# car_sheet.net
KiCad netlist of a schematic drawn in Altium Designer
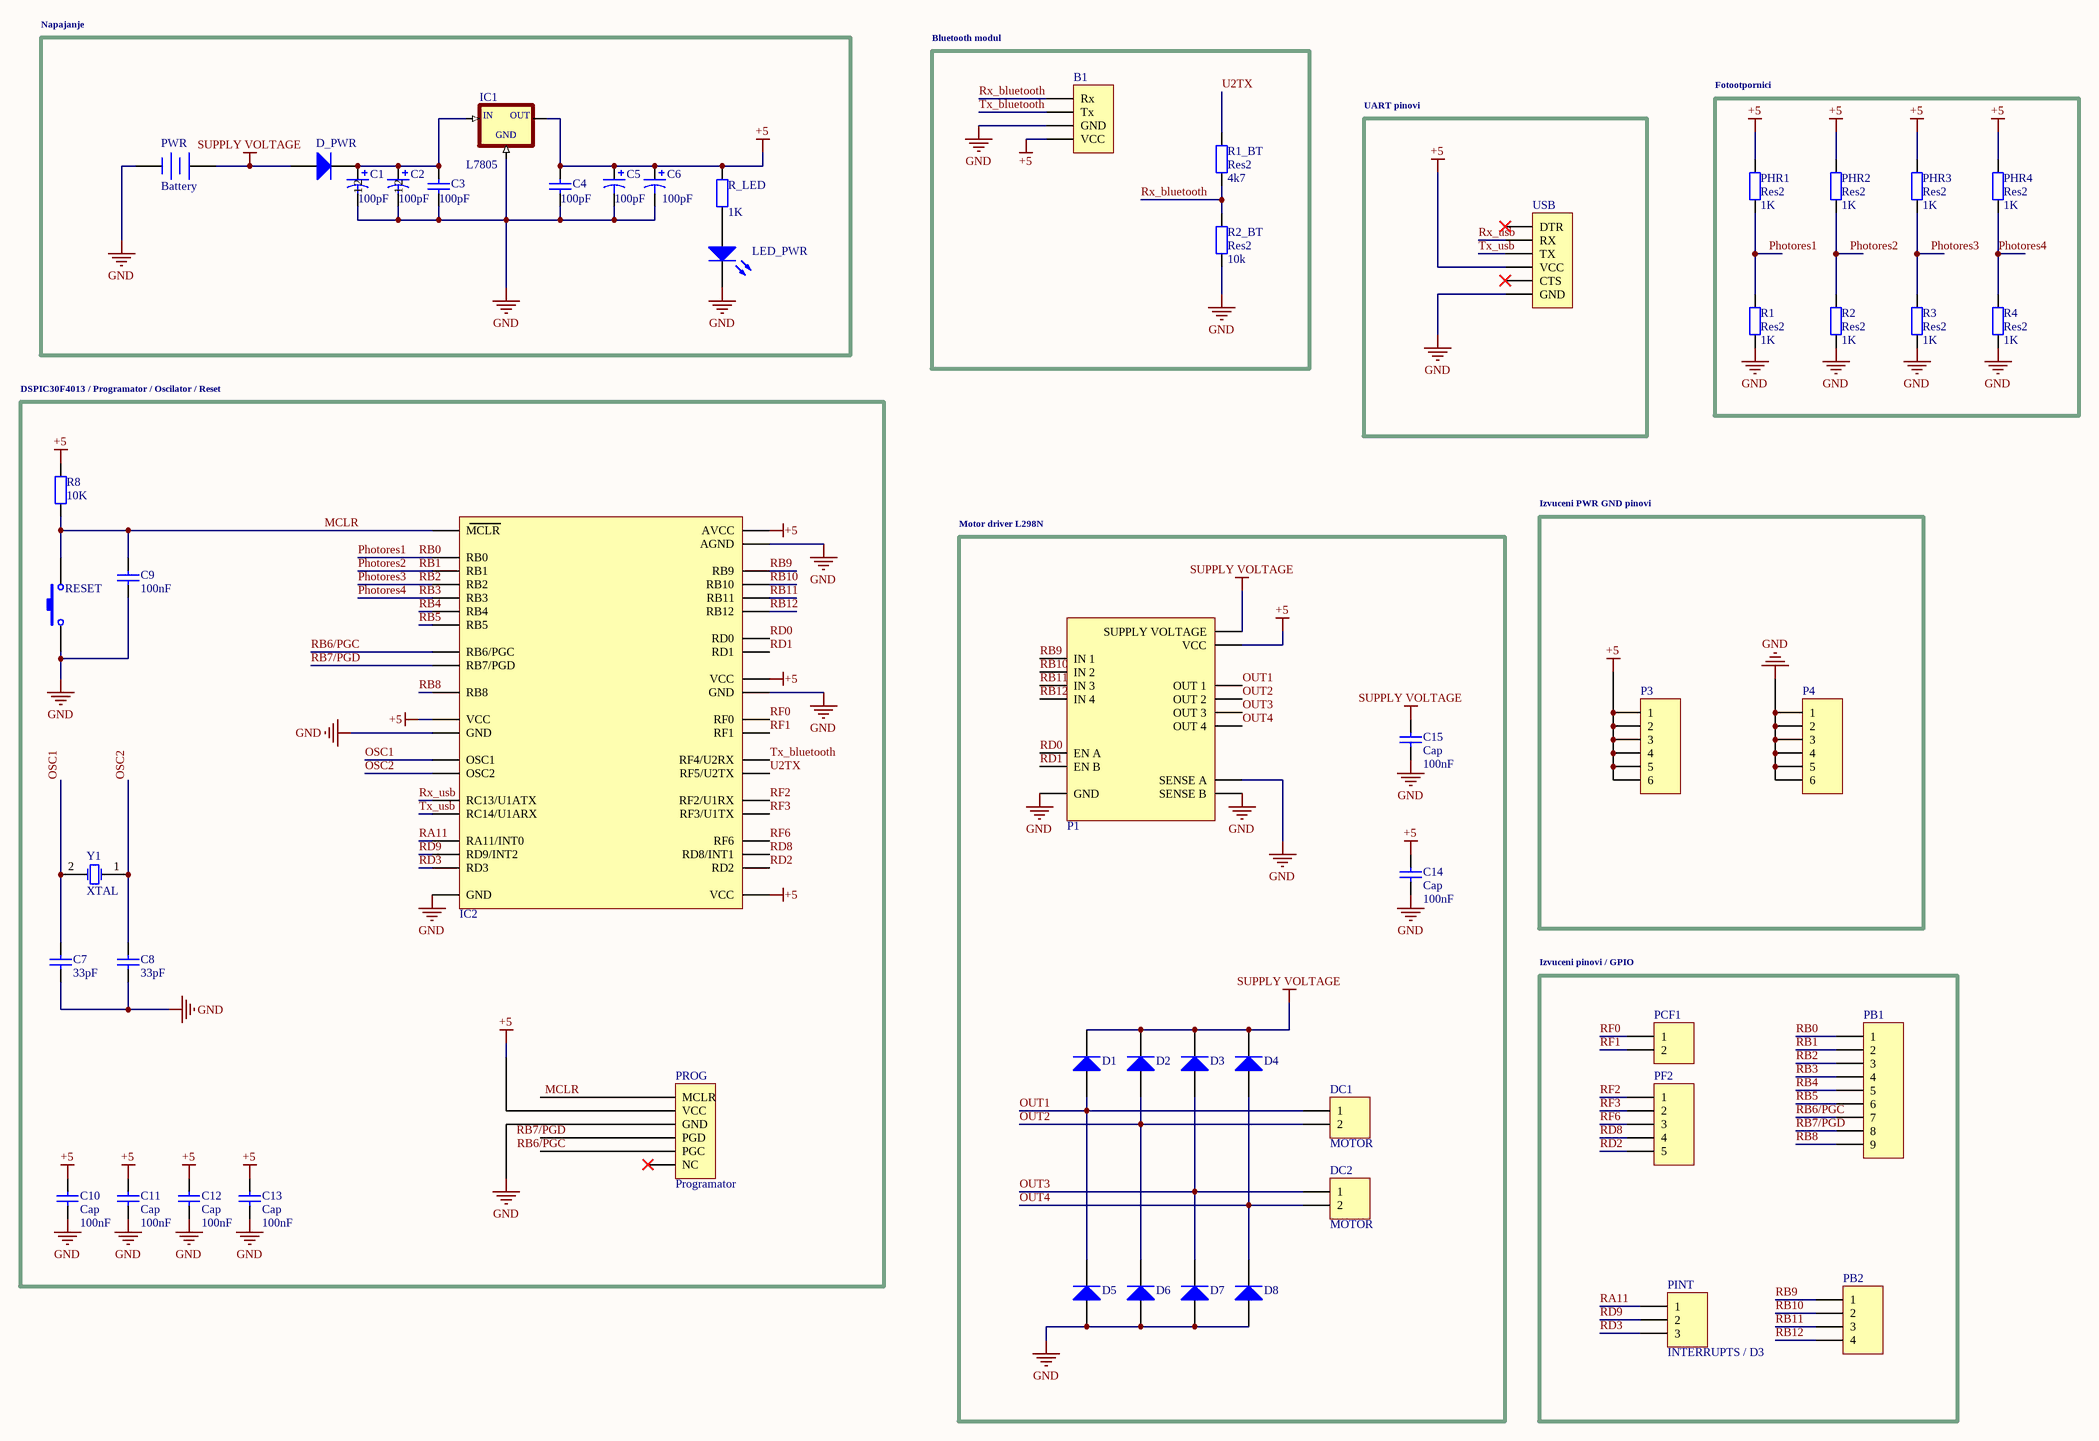
[diagram p0: car_sheet.SchDoc]

(export (version "E")
  (design (tool "Eeschema 10.0.6"))
  (components
    (comp (ref "B1")
      (value "~")
      (footprint "HDR1X4")
      (description "Header, 4-Pin")
      (fields (field (name "PUBLISHER") "Altium Limited"))
      (libsource (lib "Miscellaneous Connectors") (part "Header 4"))
    )
    (comp (ref "C1")
      (value "100pF")
      (footprint "POL_CAP")
      (description "Polarized Capacitor (Radial)")
      (fields (field (name "PUBLISHER") "Altium Limited"))
      (libsource (lib "Miscellaneous Devices") (part "Cap Pol1"))
    )
    (comp (ref "C2")
      (value "100pF")
      (footprint "POL_CAP")
      (description "Polarized Capacitor (Radial)")
      (fields (field (name "PUBLISHER") "Altium Limited"))
      (libsource (lib "Miscellaneous Devices") (part "Cap Pol1"))
    )
    (comp (ref "C3")
      (value "100pF")
      (footprint "RAD-0.3")
      (description "Capacitor")
      (fields (field (name "PUBLISHER") "Altium Limited"))
      (libsource (lib "Miscellaneous Devices") (part "Cap"))
    )
    (comp (ref "C4")
      (value "100pF")
      (footprint "RAD-0.3")
      (description "Capacitor")
      (fields (field (name "PUBLISHER") "Altium Limited"))
      (libsource (lib "Miscellaneous Devices") (part "Cap"))
    )
    (comp (ref "C5")
      (value "100pF")
      (footprint "POL_CAP")
      (description "Polarized Capacitor (Radial)")
      (fields (field (name "PUBLISHER") "Altium Limited"))
      (libsource (lib "") (part "Cap Pol1_1"))
    )
    (comp (ref "C6")
      (value "100pF")
      (footprint "POL_CAP")
      (description "Polarized Capacitor (Radial)")
      (fields (field (name "PUBLISHER") "Altium Limited"))
      (libsource (lib "") (part "Cap Pol1_1"))
    )
    (comp (ref "C7")
      (value "33pF")
      (footprint "RAD-0.3")
      (description "Capacitor")
      (fields (field (name "Comment") "Cap") (field (name "PUBLISHER") "Altium Limited"))
      (libsource (lib "Miscellaneous Devices") (part "Cap"))
    )
    (comp (ref "C8")
      (value "33pF")
      (footprint "RAD-0.3")
      (description "Capacitor")
      (fields (field (name "Comment") "Cap") (field (name "PUBLISHER") "Altium Limited"))
      (libsource (lib "Miscellaneous Devices") (part "Cap"))
    )
    (comp (ref "C9")
      (value "100nF")
      (footprint "RAD-0.3")
      (description "Capacitor")
      (fields (field (name "Comment") "Cap") (field (name "PUBLISHER") "Altium Limited"))
      (libsource (lib "Miscellaneous Devices") (part "Cap"))
    )
    (comp (ref "C10")
      (value "Cap")
      (footprint "RAD-0.3")
      (description "Capacitor")
      (fields (field (name "ALTIUM_VALUE") "100nF") (field (name "PUBLISHER") "Altium Limited"))
      (libsource (lib "Miscellaneous Devices") (part "Cap"))
    )
    (comp (ref "C11")
      (value "Cap")
      (footprint "RAD-0.3")
      (description "Capacitor")
      (fields (field (name "ALTIUM_VALUE") "100nF") (field (name "PUBLISHER") "Altium Limited"))
      (libsource (lib "Miscellaneous Devices") (part "Cap"))
    )
    (comp (ref "C12")
      (value "Cap")
      (footprint "RAD-0.3")
      (description "Capacitor")
      (fields (field (name "ALTIUM_VALUE") "100nF") (field (name "PUBLISHER") "Altium Limited"))
      (libsource (lib "Miscellaneous Devices") (part "Cap"))
    )
    (comp (ref "C13")
      (value "Cap")
      (footprint "RAD-0.3")
      (description "Capacitor")
      (fields (field (name "ALTIUM_VALUE") "100nF") (field (name "PUBLISHER") "Altium Limited"))
      (libsource (lib "Miscellaneous Devices") (part "Cap"))
    )
    (comp (ref "C14")
      (value "Cap")
      (footprint "RAD-0.3")
      (description "Capacitor")
      (fields (field (name "ALTIUM_VALUE") "100nF") (field (name "PUBLISHER") "Altium Limited"))
      (libsource (lib "Miscellaneous Devices") (part "Cap"))
    )
    (comp (ref "C15")
      (value "Cap")
      (footprint "RAD-0.3")
      (description "Capacitor")
      (fields (field (name "ALTIUM_VALUE") "100nF") (field (name "PUBLISHER") "Altium Limited"))
      (libsource (lib "Miscellaneous Devices") (part "Cap"))
    )
    (comp (ref "D1")
      (value "Diode 1N914")
      (footprint "DO-35")
      (description "High Conductance Fast Diode")
      (fields (field (name "PUBLISHER") "Altium Limited"))
      (libsource (lib "Miscellaneous Devices") (part "Diode 1N914"))
    )
    (comp (ref "D2")
      (value "Diode 1N914")
      (footprint "DO-35")
      (description "High Conductance Fast Diode")
      (fields (field (name "PUBLISHER") "Altium Limited"))
      (libsource (lib "Miscellaneous Devices") (part "Diode 1N914"))
    )
    (comp (ref "D3")
      (value "Diode 1N914")
      (footprint "DO-35")
      (description "High Conductance Fast Diode")
      (fields (field (name "PUBLISHER") "Altium Limited"))
      (libsource (lib "Miscellaneous Devices") (part "Diode 1N914"))
    )
    (comp (ref "D4")
      (value "Diode 1N914")
      (footprint "DO-35")
      (description "High Conductance Fast Diode")
      (fields (field (name "PUBLISHER") "Altium Limited"))
      (libsource (lib "Miscellaneous Devices") (part "Diode 1N914"))
    )
    (comp (ref "D5")
      (value "Diode 1N914")
      (footprint "DO-35")
      (description "High Conductance Fast Diode")
      (fields (field (name "PUBLISHER") "Altium Limited"))
      (libsource (lib "Miscellaneous Devices") (part "Diode 1N914"))
    )
    (comp (ref "D6")
      (value "Diode 1N914")
      (footprint "DO-35")
      (description "High Conductance Fast Diode")
      (fields (field (name "PUBLISHER") "Altium Limited"))
      (libsource (lib "Miscellaneous Devices") (part "Diode 1N914"))
    )
    (comp (ref "D7")
      (value "Diode 1N914")
      (footprint "DO-35")
      (description "High Conductance Fast Diode")
      (fields (field (name "PUBLISHER") "Altium Limited"))
      (libsource (lib "Miscellaneous Devices") (part "Diode 1N914"))
    )
    (comp (ref "D8")
      (value "Diode 1N914")
      (footprint "DO-35")
      (description "High Conductance Fast Diode")
      (fields (field (name "PUBLISHER") "Altium Limited"))
      (libsource (lib "Miscellaneous Devices") (part "Diode 1N914"))
    )
    (comp (ref "DC1")
      (value "MOTOR")
      (footprint "HDR1X2")
      (description "Header, 2-Pin")
      (fields (field (name "PUBLISHER") "Altium Limited"))
      (libsource (lib "Miscellaneous Connectors") (part "Header 2"))
    )
    (comp (ref "DC2")
      (value "MOTOR")
      (footprint "HDR1X2")
      (description "Header, 2-Pin")
      (fields (field (name "PUBLISHER") "Altium Limited"))
      (libsource (lib "Miscellaneous Connectors") (part "Header 2"))
    )
    (comp (ref "D_PWR")
      (value "~")
      (footprint "DO-41")
      (description "1 Amp General Purpose Rectifier")
      (fields (field (name "PUBLISHER") "Altium Limited"))
      (libsource (lib "Miscellaneous Devices") (part "Diode 1N4007"))
    )
    (comp (ref "IC1")
      (value "L7805")
      (footprint "TO-220FP_STM")
      (description "Linear Voltage Regulator IC 1 Output 1.5A D2PAK")
      (fields (field (name "MF") "STMicroelectronics"))
      (libsource (lib "L7805") (part "L7805"))
    )
    (comp (ref "IC2")
      (value "dsPIC30F4013")
      (footprint "PDIP40_600MC_MCH")
      (libsource (lib "LibLTC") (part "IC_40"))
    )
    (comp (ref "LED_PWR")
      (value "~")
      (footprint "HDR1X2")
      (description "Typical RED GaAs LED")
      (fields (field (name "PUBLISHER") "Altium Limited"))
      (libsource (lib "Miscellaneous Devices") (part "LED1"))
    )
    (comp (ref "P1") (value "L298N") (footprint "Multiwatt15_V_STM") (libsource (lib "LibRC") (part "L298N")))
    (comp (ref "P3")
      (value "~")
      (footprint "HDR1X6")
      (description "Header, 6-Pin")
      (fields (field (name "PUBLISHER") "Altium Limited"))
      (libsource (lib "Miscellaneous Connectors") (part "Header 6"))
    )
    (comp (ref "P4")
      (value "~")
      (footprint "HDR1X6")
      (description "Header, 6-Pin")
      (fields (field (name "PUBLISHER") "Altium Limited"))
      (libsource (lib "Miscellaneous Connectors") (part "Header 6"))
    )
    (comp (ref "PB1")
      (value "~")
      (footprint "HDR1X9")
      (description "Header, 9-Pin")
      (fields (field (name "PUBLISHER") "Altium Limited"))
      (libsource (lib "Miscellaneous Connectors") (part "Header 9"))
    )
    (comp (ref "PB2")
      (value "~")
      (footprint "HDR1X4")
      (description "Header, 4-Pin")
      (fields (field (name "PUBLISHER") "Altium Limited"))
      (libsource (lib "Miscellaneous Connectors") (part "Header 4"))
    )
    (comp (ref "PCF1")
      (value "~")
      (footprint "HDR1X2")
      (description "Header, 2-Pin")
      (fields (field (name "PUBLISHER") "Altium Limited"))
      (libsource (lib "Miscellaneous Connectors") (part "Header 2"))
    )
    (comp (ref "PF2")
      (value "~")
      (footprint "HDR1X5")
      (description "Header, 5-Pin")
      (fields (field (name "PUBLISHER") "Altium Limited"))
      (libsource (lib "Miscellaneous Connectors") (part "Header 5"))
    )
    (comp (ref "PHR1")
      (value "Res2")
      (footprint "AXIAL-0.4")
      (description "Resistor")
      (fields (field (name "ALTIUM_VALUE") "1K") (field (name "PUBLISHER") "Altium Limited"))
      (libsource (lib "Miscellaneous Devices") (part "Res2"))
    )
    (comp (ref "PHR2")
      (value "Res2")
      (footprint "AXIAL-0.4")
      (description "Resistor")
      (fields (field (name "ALTIUM_VALUE") "1K") (field (name "PUBLISHER") "Altium Limited"))
      (libsource (lib "Miscellaneous Devices") (part "Res2"))
    )
    (comp (ref "PHR3")
      (value "Res2")
      (footprint "AXIAL-0.4")
      (description "Resistor")
      (fields (field (name "ALTIUM_VALUE") "1K") (field (name "PUBLISHER") "Altium Limited"))
      (libsource (lib "Miscellaneous Devices") (part "Res2"))
    )
    (comp (ref "PHR4")
      (value "Res2")
      (footprint "AXIAL-0.4")
      (description "Resistor")
      (fields (field (name "ALTIUM_VALUE") "1K") (field (name "PUBLISHER") "Altium Limited"))
      (libsource (lib "Miscellaneous Devices") (part "Res2"))
    )
    (comp (ref "PINT")
      (value "INTERRUPTS / D3")
      (footprint "HDR1X3")
      (description "Header, 3-Pin")
      (fields (field (name "PUBLISHER") "Altium Limited"))
      (libsource (lib "Miscellaneous Connectors") (part "Header 3"))
    )
    (comp (ref "PROG")
      (value "Programator")
      (footprint "HDR1X6")
      (description "Header, 6-Pin")
      (fields (field (name "PUBLISHER") "Altium Limited"))
      (libsource (lib "Miscellaneous Connectors") (part "Header 6"))
    )
    (comp (ref "PWR")
      (value "Battery")
      (footprint "BAT-2")
      (description "Multicell Battery")
      (fields (field (name "PUBLISHER") "Altium Limited"))
      (libsource (lib "Miscellaneous Devices") (part "Battery"))
    )
    (comp (ref "R1")
      (value "Res2")
      (footprint "AXIAL-0.4")
      (description "Resistor")
      (fields (field (name "ALTIUM_VALUE") "1K") (field (name "PUBLISHER") "Altium Limited"))
      (libsource (lib "Miscellaneous Devices") (part "Res2"))
    )
    (comp (ref "R1_BT")
      (value "Res2")
      (footprint "AXIAL-0.4")
      (description "Resistor")
      (fields (field (name "ALTIUM_VALUE") "4k7") (field (name "PUBLISHER") "Altium Limited"))
      (libsource (lib "Miscellaneous Devices") (part "Res2"))
    )
    (comp (ref "R2")
      (value "Res2")
      (footprint "AXIAL-0.4")
      (description "Resistor")
      (fields (field (name "ALTIUM_VALUE") "1K") (field (name "PUBLISHER") "Altium Limited"))
      (libsource (lib "Miscellaneous Devices") (part "Res2"))
    )
    (comp (ref "R2_BT")
      (value "Res2")
      (footprint "AXIAL-0.4")
      (description "Resistor")
      (fields (field (name "ALTIUM_VALUE") "10k") (field (name "PUBLISHER") "Altium Limited"))
      (libsource (lib "Miscellaneous Devices") (part "Res2"))
    )
    (comp (ref "R3")
      (value "Res2")
      (footprint "AXIAL-0.4")
      (description "Resistor")
      (fields (field (name "ALTIUM_VALUE") "1K") (field (name "PUBLISHER") "Altium Limited"))
      (libsource (lib "Miscellaneous Devices") (part "Res2"))
    )
    (comp (ref "R4")
      (value "Res2")
      (footprint "AXIAL-0.4")
      (description "Resistor")
      (fields (field (name "ALTIUM_VALUE") "1K") (field (name "PUBLISHER") "Altium Limited"))
      (libsource (lib "Miscellaneous Devices") (part "Res2"))
    )
    (comp (ref "R8")
      (value "10K")
      (footprint "AXIAL-0.4")
      (description "Resistor")
      (fields (field (name "Comment") "Res2") (field (name "PUBLISHER") "Altium Limited"))
      (libsource (lib "Miscellaneous Devices") (part "Res2"))
    )
    (comp (ref "RESET")
      (value "SW-PB")
      (footprint "SPST-2")
      (description "Switch")
      (fields (field (name "PUBLISHER") "Altium Limited"))
      (libsource (lib "Miscellaneous Devices") (part "SW-PB"))
    )
    (comp (ref "R_LED")
      (value "1K")
      (footprint "AXIAL-0.4")
      (description "Resistor")
      (fields (field (name "PUBLISHER") "Altium Limited"))
      (libsource (lib "Miscellaneous Devices") (part "Res2"))
    )
    (comp (ref "USB")
      (value "~")
      (footprint "HDR1X6")
      (description "Header, 6-Pin")
      (fields (field (name "PUBLISHER") "Altium Limited"))
      (libsource (lib "Miscellaneous Connectors") (part "Header 6"))
    )
    (comp (ref "Y1")
      (value "XTAL")
      (footprint "R38")
      (description "Crystal Oscillator")
      (fields (field (name "PUBLISHER") "Altium Limited"))
      (libsource (lib "Miscellaneous Devices") (part "XTAL"))
    )
  )
  (nets
    (net (code "1") (name "+5") (class "Default")
      (node (ref "B1") (pin "4") (pinfunction "4_4") (pintype "passive"))
      (node (ref "C10") (pin "1") (pinfunction "1_1") (pintype "passive"))
      (node (ref "C11") (pin "2") (pinfunction "2_2") (pintype "passive"))
      (node (ref "C12") (pin "2") (pinfunction "2_2") (pintype "passive"))
      (node (ref "C13") (pin "2") (pinfunction "2_2") (pintype "passive"))
      (node (ref "C14") (pin "2") (pinfunction "2_2") (pintype "passive"))
      (node (ref "C4") (pin "2") (pinfunction "2_2") (pintype "passive"))
      (node (ref "C5") (pin "1") (pinfunction "1_1") (pintype "passive"))
      (node (ref "C6") (pin "1") (pinfunction "1_1") (pintype "passive"))
      (node (ref "IC1") (pin "3") (pinfunction "OUT_3") (pintype "passive"))
      (node (ref "IC2") (pin "11") (pinfunction "VCC_11") (pintype "passive"))
      (node (ref "IC2") (pin "21") (pinfunction "VCC_21") (pintype "passive"))
      (node (ref "IC2") (pin "32") (pinfunction "VCC_32") (pintype "passive"))
      (node (ref "IC2") (pin "40") (pinfunction "AVCC_40") (pintype "passive"))
      (node (ref "P1") (pin "9") (pinfunction "VCC_9") (pintype "passive"))
      (node (ref "P3") (pin "1") (pinfunction "1_1") (pintype "passive"))
      (node (ref "P3") (pin "2") (pinfunction "2_2") (pintype "passive"))
      (node (ref "P3") (pin "3") (pinfunction "3_3") (pintype "passive"))
      (node (ref "P3") (pin "4") (pinfunction "4_4") (pintype "passive"))
      (node (ref "P3") (pin "5") (pinfunction "5_5") (pintype "passive"))
      (node (ref "P3") (pin "6") (pinfunction "6_6") (pintype "passive"))
      (node (ref "PHR1") (pin "2") (pinfunction "2_2") (pintype "passive"))
      (node (ref "PHR2") (pin "2") (pinfunction "2_2") (pintype "passive"))
      (node (ref "PHR3") (pin "2") (pinfunction "2_2") (pintype "passive"))
      (node (ref "PHR4") (pin "2") (pinfunction "2_2") (pintype "passive"))
      (node (ref "PROG") (pin "2") (pinfunction "2_2") (pintype "passive"))
      (node (ref "R8") (pin "2") (pinfunction "2_2") (pintype "passive"))
      (node (ref "R_LED") (pin "2") (pinfunction "2_2") (pintype "passive"))
      (node (ref "USB") (pin "4") (pinfunction "4_4") (pintype "passive"))
    )
    (net (code "2") (name "/MCLR") (class "Default")
      (node (ref "C9") (pin "1") (pinfunction "1_1") (pintype "passive"))
      (node (ref "IC2") (pin "1") (pinfunction "MCLR_1") (pintype "passive"))
      (node (ref "PROG") (pin "1") (pinfunction "1_1") (pintype "passive"))
      (node (ref "R8") (pin "1") (pinfunction "1_1") (pintype "passive"))
      (node (ref "RESET") (pin "2") (pinfunction "2_2") (pintype "passive"))
    )
    (net (code "3") (name "/OSC1") (class "Default")
      (node (ref "C7") (pin "2") (pinfunction "2_2") (pintype "passive"))
      (node (ref "IC2") (pin "13") (pinfunction "OSC1_13") (pintype "passive"))
      (node (ref "Y1") (pin "2") (pinfunction "OSC2_2") (pintype "passive"))
    )
    (net (code "4") (name "/OSC2") (class "Default")
      (node (ref "C8") (pin "2") (pinfunction "2_2") (pintype "passive"))
      (node (ref "IC2") (pin "14") (pinfunction "OSC2_14") (pintype "passive"))
      (node (ref "Y1") (pin "1") (pinfunction "OSC1_1") (pintype "passive"))
    )
    (net (code "5") (name "/OUT1") (class "Default")
      (node (ref "D1") (pin "1") (pinfunction "A_1") (pintype "passive"))
      (node (ref "D5") (pin "2") (pinfunction "K_2") (pintype "passive"))
      (node (ref "DC1") (pin "1") (pinfunction "1_1") (pintype "passive"))
      (node (ref "P1") (pin "2") (pinfunction "OUT_1_2") (pintype "passive"))
    )
    (net (code "6") (name "/OUT2") (class "Default")
      (node (ref "D2") (pin "1") (pinfunction "A_1") (pintype "passive"))
      (node (ref "D6") (pin "2") (pinfunction "K_2") (pintype "passive"))
      (node (ref "DC1") (pin "2") (pinfunction "2_2") (pintype "passive"))
      (node (ref "P1") (pin "3") (pinfunction "OUT_2_3") (pintype "passive"))
    )
    (net (code "7") (name "/OUT3") (class "Default")
      (node (ref "D3") (pin "1") (pinfunction "A_1") (pintype "passive"))
      (node (ref "D7") (pin "2") (pinfunction "K_2") (pintype "passive"))
      (node (ref "DC2") (pin "1") (pinfunction "1_1") (pintype "passive"))
      (node (ref "P1") (pin "13") (pinfunction "OUT_3_13") (pintype "passive"))
    )
    (net (code "8") (name "/OUT4") (class "Default")
      (node (ref "D4") (pin "1") (pinfunction "A_1") (pintype "passive"))
      (node (ref "D8") (pin "2") (pinfunction "K_2") (pintype "passive"))
      (node (ref "DC2") (pin "2") (pinfunction "2_2") (pintype "passive"))
      (node (ref "P1") (pin "14") (pinfunction "OUT_4_14") (pintype "passive"))
    )
    (net (code "9") (name "/Photores1") (class "Default")
      (node (ref "IC2") (pin "2") (pinfunction "RB0_2") (pintype "passive"))
      (node (ref "PB1") (pin "1") (pinfunction "1_1") (pintype "passive"))
      (node (ref "PHR1") (pin "1") (pinfunction "1_1") (pintype "passive"))
      (node (ref "R1") (pin "2") (pinfunction "2_2") (pintype "passive"))
    )
    (net (code "10") (name "/Photores2") (class "Default")
      (node (ref "IC2") (pin "3") (pinfunction "RB1_3") (pintype "passive"))
      (node (ref "PB1") (pin "2") (pinfunction "2_2") (pintype "passive"))
      (node (ref "PHR2") (pin "1") (pinfunction "1_1") (pintype "passive"))
      (node (ref "R2") (pin "2") (pinfunction "2_2") (pintype "passive"))
    )
    (net (code "11") (name "/Photores3") (class "Default")
      (node (ref "IC2") (pin "4") (pinfunction "RB2_4") (pintype "passive"))
      (node (ref "PB1") (pin "3") (pinfunction "3_3") (pintype "passive"))
      (node (ref "PHR3") (pin "1") (pinfunction "1_1") (pintype "passive"))
      (node (ref "R3") (pin "2") (pinfunction "2_2") (pintype "passive"))
    )
    (net (code "12") (name "/Photores4") (class "Default")
      (node (ref "IC2") (pin "5") (pinfunction "RB3_5") (pintype "passive"))
      (node (ref "PB1") (pin "4") (pinfunction "4_4") (pintype "passive"))
      (node (ref "PHR4") (pin "1") (pinfunction "1_1") (pintype "passive"))
      (node (ref "R4") (pin "2") (pinfunction "2_2") (pintype "passive"))
    )
    (net (code "13") (name "/RA11") (class "Default")
      (node (ref "IC2") (pin "17") (pinfunction "RA11/INT0_17") (pintype "passive"))
      (node (ref "PINT") (pin "1") (pinfunction "1_1") (pintype "passive"))
    )
    (net (code "14") (name "/RB4") (class "Default")
      (node (ref "IC2") (pin "6") (pinfunction "RB4_6") (pintype "passive"))
      (node (ref "PB1") (pin "5") (pinfunction "5_5") (pintype "passive"))
    )
    (net (code "15") (name "/RB5") (class "Default")
      (node (ref "IC2") (pin "7") (pinfunction "RB5_7") (pintype "passive"))
      (node (ref "PB1") (pin "6") (pinfunction "6_6") (pintype "passive"))
    )
    (net (code "16") (name "/RB6{slash}PGC") (class "Default")
      (node (ref "IC2") (pin "8") (pinfunction "RB6/PGC_8") (pintype "passive"))
      (node (ref "PB1") (pin "7") (pinfunction "7_7") (pintype "passive"))
      (node (ref "PROG") (pin "5") (pinfunction "5_5") (pintype "passive"))
    )
    (net (code "17") (name "/RB7{slash}PGD") (class "Default")
      (node (ref "IC2") (pin "9") (pinfunction "RB7/PGD_9") (pintype "passive"))
      (node (ref "PB1") (pin "8") (pinfunction "8_8") (pintype "passive"))
      (node (ref "PROG") (pin "4") (pinfunction "4_4") (pintype "passive"))
    )
    (net (code "18") (name "/RB8") (class "Default")
      (node (ref "IC2") (pin "10") (pinfunction "RB8_10") (pintype "passive"))
      (node (ref "PB1") (pin "9") (pinfunction "9_9") (pintype "passive"))
    )
    (net (code "19") (name "/RB9") (class "Default")
      (node (ref "IC2") (pin "38") (pinfunction "RB9_38") (pintype "passive"))
      (node (ref "P1") (pin "5") (pinfunction "IN_1_5") (pintype "passive"))
      (node (ref "PB2") (pin "1") (pinfunction "1_1") (pintype "passive"))
    )
    (net (code "20") (name "/RB10") (class "Default")
      (node (ref "IC2") (pin "37") (pinfunction "RB10_37") (pintype "passive"))
      (node (ref "P1") (pin "7") (pinfunction "IN_2_7") (pintype "passive"))
      (node (ref "PB2") (pin "2") (pinfunction "2_2") (pintype "passive"))
    )
    (net (code "21") (name "/RB11") (class "Default")
      (node (ref "IC2") (pin "36") (pinfunction "RB11_36") (pintype "passive"))
      (node (ref "P1") (pin "10") (pinfunction "IN_3_10") (pintype "passive"))
      (node (ref "PB2") (pin "3") (pinfunction "3_3") (pintype "passive"))
    )
    (net (code "22") (name "/RB12") (class "Default")
      (node (ref "IC2") (pin "35") (pinfunction "RB12_35") (pintype "passive"))
      (node (ref "P1") (pin "12") (pinfunction "IN_4_12") (pintype "passive"))
      (node (ref "PB2") (pin "4") (pinfunction "4_4") (pintype "passive"))
    )
    (net (code "23") (name "/RD0") (class "Default")
      (node (ref "IC2") (pin "34") (pinfunction "RD0_34") (pintype "passive"))
      (node (ref "P1") (pin "6") (pinfunction "EN_A_6") (pintype "passive"))
    )
    (net (code "24") (name "/RD1") (class "Default")
      (node (ref "IC2") (pin "33") (pinfunction "RD1_33") (pintype "passive"))
      (node (ref "P1") (pin "11") (pinfunction "EN_B_11") (pintype "passive"))
    )
    (net (code "25") (name "/RD2") (class "Default")
      (node (ref "IC2") (pin "22") (pinfunction "RD2_22") (pintype "passive"))
      (node (ref "PF2") (pin "5") (pinfunction "5_5") (pintype "passive"))
    )
    (net (code "26") (name "/RD3") (class "Default")
      (node (ref "IC2") (pin "19") (pinfunction "RD3_19") (pintype "passive"))
      (node (ref "PINT") (pin "3") (pinfunction "3_3") (pintype "passive"))
    )
    (net (code "27") (name "/RD8") (class "Default")
      (node (ref "IC2") (pin "23") (pinfunction "RD8/INT1_23") (pintype "passive"))
      (node (ref "PF2") (pin "4") (pinfunction "4_4") (pintype "passive"))
    )
    (net (code "28") (name "/RD9") (class "Default")
      (node (ref "IC2") (pin "18") (pinfunction "RD9/INT2_18") (pintype "passive"))
      (node (ref "PINT") (pin "2") (pinfunction "2_2") (pintype "passive"))
    )
    (net (code "29") (name "/RF0") (class "Default")
      (node (ref "IC2") (pin "30") (pinfunction "RF0_30") (pintype "passive"))
      (node (ref "PCF1") (pin "1") (pinfunction "1_1") (pintype "passive"))
    )
    (net (code "30") (name "/RF1") (class "Default")
      (node (ref "IC2") (pin "29") (pinfunction "RF1_29") (pintype "passive"))
      (node (ref "PCF1") (pin "2") (pinfunction "2_2") (pintype "passive"))
    )
    (net (code "31") (name "/RF2") (class "Default")
      (node (ref "IC2") (pin "26") (pinfunction "RF2/U1RX_26") (pintype "passive"))
      (node (ref "PF2") (pin "1") (pinfunction "1_1") (pintype "passive"))
    )
    (net (code "32") (name "/RF3") (class "Default")
      (node (ref "IC2") (pin "25") (pinfunction "RF3/U1TX_25") (pintype "passive"))
      (node (ref "PF2") (pin "2") (pinfunction "2_2") (pintype "passive"))
    )
    (net (code "33") (name "/RF6") (class "Default")
      (node (ref "IC2") (pin "24") (pinfunction "RF6_24") (pintype "passive"))
      (node (ref "PF2") (pin "3") (pinfunction "3_3") (pintype "passive"))
    )
    (net (code "34") (name "/Rx_bluetooth") (class "Default")
      (node (ref "B1") (pin "1") (pinfunction "1_1") (pintype "passive"))
      (node (ref "R1_BT") (pin "1") (pinfunction "1_1") (pintype "passive"))
      (node (ref "R2_BT") (pin "2") (pinfunction "2_2") (pintype "passive"))
    )
    (net (code "35") (name "/Rx_usb") (class "Default")
      (node (ref "IC2") (pin "15") (pinfunction "RC13/U1ATX_15") (pintype "passive"))
      (node (ref "USB") (pin "2") (pinfunction "2_2") (pintype "passive"))
    )
    (net (code "36") (name "/Tx_bluetooth") (class "Default")
      (node (ref "B1") (pin "2") (pinfunction "2_2") (pintype "passive"))
      (node (ref "IC2") (pin "28") (pinfunction "RF4/U2RX_28") (pintype "passive"))
    )
    (net (code "37") (name "/Tx_usb") (class "Default")
      (node (ref "IC2") (pin "16") (pinfunction "RC14/U1ARX_16") (pintype "passive"))
      (node (ref "USB") (pin "3") (pinfunction "3_3") (pintype "passive"))
    )
    (net (code "38") (name "/U2TX") (class "Default")
      (node (ref "IC2") (pin "27") (pinfunction "RF5/U2TX_27") (pintype "passive"))
      (node (ref "R1_BT") (pin "2") (pinfunction "2_2") (pintype "passive"))
    )
    (net (code "39") (name "GND") (class "Default")
      (node (ref "B1") (pin "3") (pinfunction "3_3") (pintype "passive"))
      (node (ref "C1") (pin "2") (pinfunction "2_2") (pintype "passive"))
      (node (ref "C10") (pin "2") (pinfunction "2_2") (pintype "passive"))
      (node (ref "C11") (pin "1") (pinfunction "1_1") (pintype "passive"))
      (node (ref "C12") (pin "1") (pinfunction "1_1") (pintype "passive"))
      (node (ref "C13") (pin "1") (pinfunction "1_1") (pintype "passive"))
      (node (ref "C14") (pin "1") (pinfunction "1_1") (pintype "passive"))
      (node (ref "C15") (pin "1") (pinfunction "1_1") (pintype "passive"))
      (node (ref "C2") (pin "2") (pinfunction "2_2") (pintype "passive"))
      (node (ref "C3") (pin "1") (pinfunction "1_1") (pintype "passive"))
      (node (ref "C4") (pin "1") (pinfunction "1_1") (pintype "passive"))
      (node (ref "C5") (pin "2") (pinfunction "2_2") (pintype "passive"))
      (node (ref "C6") (pin "2") (pinfunction "2_2") (pintype "passive"))
      (node (ref "C7") (pin "1") (pinfunction "1_1") (pintype "passive"))
      (node (ref "C8") (pin "1") (pinfunction "1_1") (pintype "passive"))
      (node (ref "C9") (pin "2") (pinfunction "2_2") (pintype "passive"))
      (node (ref "D5") (pin "1") (pinfunction "A_1") (pintype "passive"))
      (node (ref "D6") (pin "1") (pinfunction "A_1") (pintype "passive"))
      (node (ref "D7") (pin "1") (pinfunction "A_1") (pintype "passive"))
      (node (ref "D8") (pin "1") (pinfunction "A_1") (pintype "passive"))
      (node (ref "IC1") (pin "2") (pinfunction "GND_2") (pintype "input"))
      (node (ref "IC2") (pin "12") (pinfunction "GND_12") (pintype "passive"))
      (node (ref "IC2") (pin "20") (pinfunction "GND_20") (pintype "passive"))
      (node (ref "IC2") (pin "31") (pinfunction "GND_31") (pintype "passive"))
      (node (ref "IC2") (pin "39") (pinfunction "AGND_39") (pintype "passive"))
      (node (ref "LED_PWR") (pin "2") (pinfunction "K_2") (pintype "passive"))
      (node (ref "P1") (pin "1") (pinfunction "SENSE_A_1") (pintype "passive"))
      (node (ref "P1") (pin "15") (pinfunction "SENSE_B_15") (pintype "passive"))
      (node (ref "P1") (pin "8") (pinfunction "GND_8") (pintype "passive"))
      (node (ref "P4") (pin "1") (pinfunction "1_1") (pintype "passive"))
      (node (ref "P4") (pin "2") (pinfunction "2_2") (pintype "passive"))
      (node (ref "P4") (pin "3") (pinfunction "3_3") (pintype "passive"))
      (node (ref "P4") (pin "4") (pinfunction "4_4") (pintype "passive"))
      (node (ref "P4") (pin "5") (pinfunction "5_5") (pintype "passive"))
      (node (ref "P4") (pin "6") (pinfunction "6_6") (pintype "passive"))
      (node (ref "PROG") (pin "3") (pinfunction "3_3") (pintype "passive"))
      (node (ref "PWR") (pin "2") (pinfunction "-_2") (pintype "passive"))
      (node (ref "R1") (pin "1") (pinfunction "1_1") (pintype "passive"))
      (node (ref "R2") (pin "1") (pinfunction "1_1") (pintype "passive"))
      (node (ref "R2_BT") (pin "1") (pinfunction "1_1") (pintype "passive"))
      (node (ref "R3") (pin "1") (pinfunction "1_1") (pintype "passive"))
      (node (ref "R4") (pin "1") (pinfunction "1_1") (pintype "passive"))
      (node (ref "RESET") (pin "1") (pinfunction "1_1") (pintype "passive"))
      (node (ref "USB") (pin "6") (pinfunction "6_6") (pintype "passive"))
    )
    (net (code "40") (name "Net-(D_PWR-K)") (class "Default")
      (node (ref "C1") (pin "1") (pinfunction "1_1") (pintype "passive"))
      (node (ref "C2") (pin "1") (pinfunction "1_1") (pintype "passive"))
      (node (ref "C3") (pin "2") (pinfunction "2_2") (pintype "passive"))
      (node (ref "D_PWR") (pin "2") (pinfunction "K_2") (pintype "passive"))
      (node (ref "IC1") (pin "1") (pinfunction "IN_1") (pintype "input"))
    )
    (net (code "41") (name "Net-(LED_PWR-A)") (class "Default")
      (node (ref "LED_PWR") (pin "1") (pinfunction "A_1") (pintype "passive"))
      (node (ref "R_LED") (pin "1") (pinfunction "1_1") (pintype "passive"))
    )
    (net (code "42") (name "SUPPLY VOLTAGE") (class "Default")
      (node (ref "C15") (pin "2") (pinfunction "2_2") (pintype "passive"))
      (node (ref "D1") (pin "2") (pinfunction "K_2") (pintype "passive"))
      (node (ref "D2") (pin "2") (pinfunction "K_2") (pintype "passive"))
      (node (ref "D3") (pin "2") (pinfunction "K_2") (pintype "passive"))
      (node (ref "D4") (pin "2") (pinfunction "K_2") (pintype "passive"))
      (node (ref "D_PWR") (pin "1") (pinfunction "A_1") (pintype "passive"))
      (node (ref "P1") (pin "4") (pinfunction "SUPPLY_VOLTAGE_4") (pintype "passive"))
      (node (ref "PWR") (pin "1") (pinfunction "+_1") (pintype "passive"))
    )
    (net (code "43") (name "unconnected-(PROG-Pad6)") (class "Default")
      (node (ref "PROG") (pin "6") (pinfunction "6_6") (pintype "passive+no_connect"))
    )
    (net (code "44") (name "unconnected-(USB-Pad1)") (class "Default")
      (node (ref "USB") (pin "1") (pinfunction "1_1") (pintype "passive+no_connect"))
    )
    (net (code "45") (name "unconnected-(USB-Pad5)") (class "Default")
      (node (ref "USB") (pin "5") (pinfunction "5_5") (pintype "passive+no_connect"))
    )
  )
)
